# STM8S005C6_Footsprint.net
KiCad netlist of a schematic drawn in Altium Designer
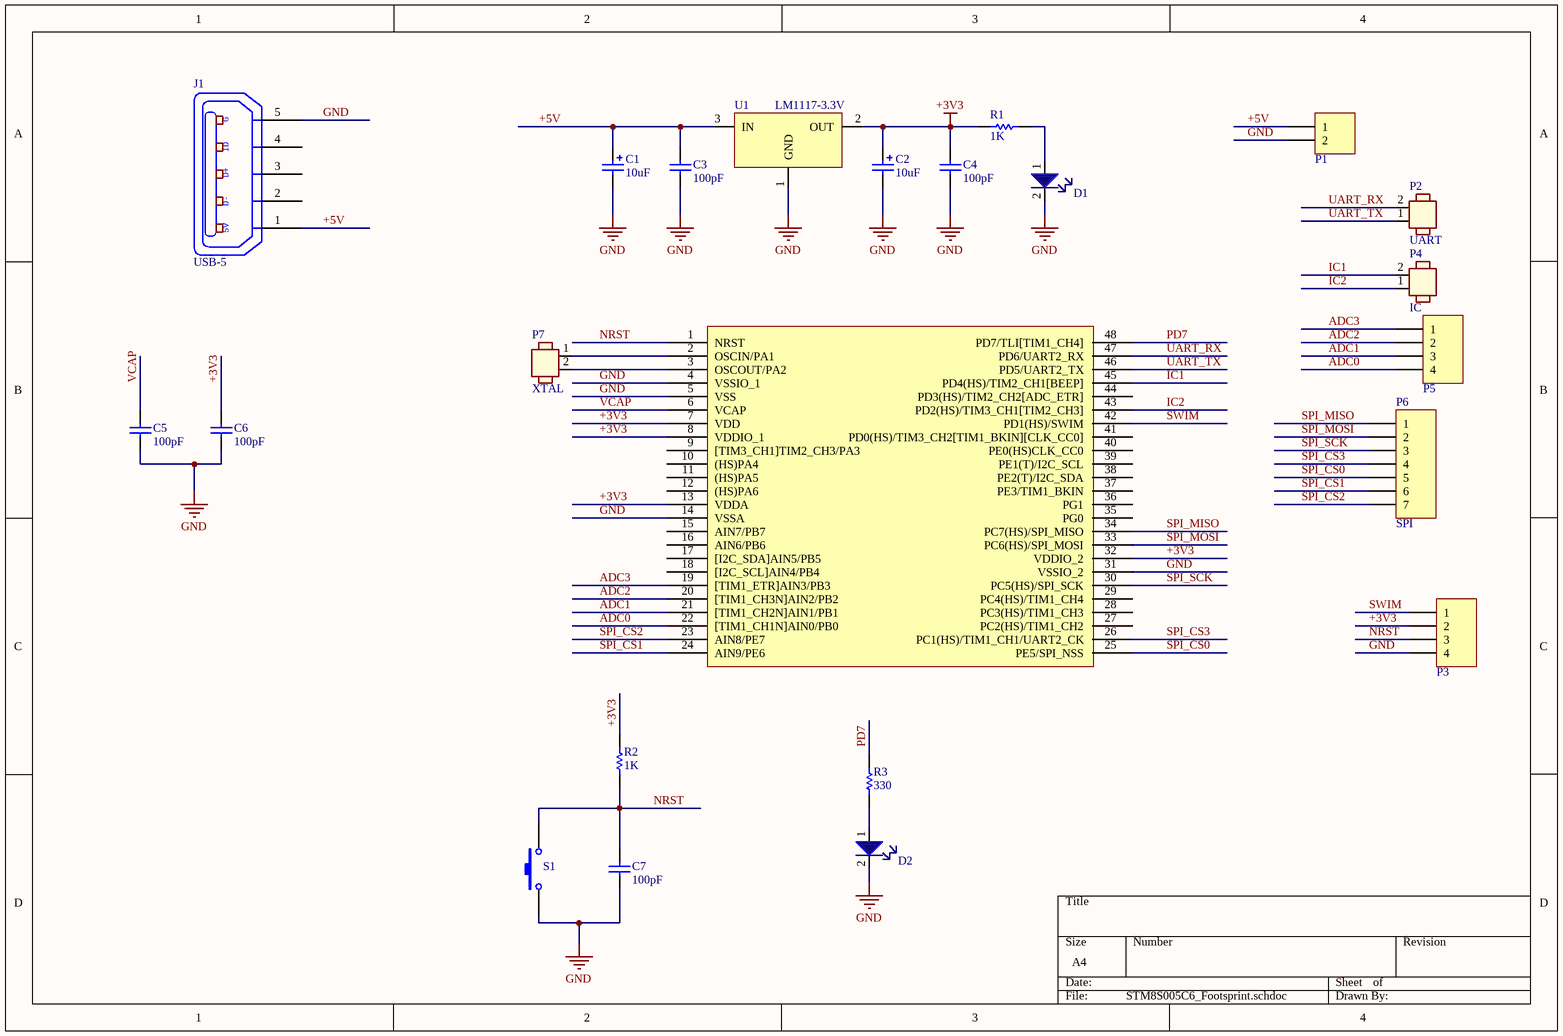
[diagram p0: STM8S005C6_Footsprint.schdoc]

(export (version "E")
  (design (tool "Eeschema 10.0.6"))
  (components
    (comp (ref "C1")
      (value "10uF")
      (footprint "CP1/2")
      (description "Polarized Capacitor (Radial)")
      (fields (field (name "Comment") "Cap Pol"))
      (libsource (lib "PIF_Library") (part "Cap Pol"))
    )
    (comp (ref "C2")
      (value "10uF")
      (footprint "CP1/2")
      (description "Polarized Capacitor (Radial)")
      (fields (field (name "Comment") "Cap Pol"))
      (libsource (lib "PIF_Library") (part "Cap Pol"))
    )
    (comp (ref "C3")
      (value "100pF")
      (footprint "CAP-SM-0805")
      (description "Capacitor")
      (fields (field (name "Comment") "Cap Non-Pol SMD"))
      (libsource (lib "PIF_Library") (part "Cap Non-Pol SMD"))
    )
    (comp (ref "C4")
      (value "100pF")
      (footprint "CAP-SM-0805")
      (description "Capacitor")
      (fields (field (name "Comment") "Cap Non-Pol SMD"))
      (libsource (lib "PIF_Library") (part "Cap Non-Pol SMD"))
    )
    (comp (ref "C5")
      (value "100pF")
      (footprint "CAP-SM-0805")
      (description "Capacitor")
      (fields (field (name "Comment") "Cap Non-Pol SMD"))
      (libsource (lib "PIF_Library") (part "Cap Non-Pol SMD"))
    )
    (comp (ref "C6")
      (value "100pF")
      (footprint "CAP-SM-0805")
      (description "Capacitor")
      (fields (field (name "Comment") "Cap Non-Pol SMD"))
      (libsource (lib "PIF_Library") (part "Cap Non-Pol SMD"))
    )
    (comp (ref "C7")
      (value "100pF")
      (footprint "CAP-SM-0805")
      (description "Capacitor")
      (fields (field (name "Comment") "Cap Non-Pol SMD"))
      (libsource (lib "PIF_Library") (part "Cap Non-Pol SMD"))
    )
    (comp (ref "D1") (value "LED") (footprint "LED 3mm") (libsource (lib "C15") (part "LED")))
    (comp (ref "D2") (value "LED") (footprint "LED 3mm") (libsource (lib "C15") (part "LED")))
    (comp (ref "J1")
      (value "USB-5")
      (footprint "USB-M2")
      (fields
        (field (name "MANUFACTURER") "FCI")
        (field (name "MANUFACTURER PART NUMBER") "10118193-0001LF")
        (field (name ".CREATOR") "MM")
        (field (name ".CHECKED PCB") "RF")
        (field (name ".CHECKED SCH") "MM")
      )
      (libsource (lib "LIBRARY") (part "USB-5"))
    )
    (comp (ref "P1")
      (value "Header 2")
      (footprint "JP2")
      (description "Header, 2-Pin")
      (fields (field (name "PUBLISHER") "Altium Limited"))
      (libsource (lib "PIF_Library") (part "Header 2"))
    )
    (comp (ref "P2") (value "UART") (footprint "HDR 2x1") (libsource (lib "C15") (part "Header 2")))
    (comp (ref "P3")
      (value "Header 4")
      (footprint "JP4")
      (description "Header, 4-Pin")
      (fields (field (name "PUBLISHER") "Altium Limited"))
      (libsource (lib "PIF_Library") (part "Header 4"))
    )
    (comp (ref "P4") (value "IC") (footprint "HDR 2x1") (libsource (lib "C15") (part "Header 2")))
    (comp (ref "P5")
      (value "Header 4")
      (footprint "JP4")
      (description "Header, 4-Pin")
      (fields (field (name "PUBLISHER") "Altium Limited"))
      (libsource (lib "PIF_Library") (part "Header 4"))
    )
    (comp (ref "P6")
      (value "SPI")
      (footprint "HDR1X7")
      (description "Header, 7-Pin")
      (fields (field (name "PUBLISHER") "Altium Limited"))
      (libsource (lib "NBBLib 14-03-2012") (part "Header 7"))
    )
    (comp (ref "P7") (value "XTAL") (footprint "HDR 2x1") (libsource (lib "") (part "Header 2_1")))
    (comp (ref "R1")
      (value "1K")
      (footprint "RES-SM-0805")
      (description "Resistor")
      (fields (field (name "Comment") "RESISTOR SMD"))
      (libsource (lib "PIF_Library") (part "RESISTOR SMD"))
    )
    (comp (ref "R2")
      (value "1K")
      (footprint "RES-SM-0805")
      (description "Resistor")
      (fields (field (name "Comment") "RESISTOR SMD"))
      (libsource (lib "PIF_Library") (part "RESISTOR SMD"))
    )
    (comp (ref "R3")
      (value "330")
      (footprint "RES-SM-0805")
      (description "Resistor")
      (fields (field (name "Comment") "RESISTOR SMD"))
      (libsource (lib "PIF_Library") (part "RESISTOR SMD"))
    )
    (comp (ref "S1")
      (value "Tact SW - 2Pin")
      (footprint "SW2")
      (description "Switch button 2 pin")
      (libsource (lib "PIF_Library") (part "Tact SW - 2Pin"))
    )
    (comp (ref "U1")
      (value "LM1117-3.3V")
      (footprint "SOT223")
      (description "800mA Low-Dropout Linear Regulator")
      (fields (field (name "CREATOR") "Nguyen Ba Bien"))
      (libsource (lib "LIBRARY") (part "LM1117"))
    )
    (comp (ref "U2")
      (value "STM8S005C6")
      (footprint "STM8S005C6")
      (libsource (lib "syhaunguyen") (part "STM8S005C6"))
    )
  )
  (nets
    (net (code "1") (name "+3V3") (class "Default")
      (node (ref "C2") (pin "1") (pinfunction "1_1") (pintype "passive"))
      (node (ref "C4") (pin "1") (pinfunction "1_1") (pintype "passive"))
      (node (ref "C6") (pin "1") (pinfunction "1_1") (pintype "passive"))
      (node (ref "P3") (pin "2") (pinfunction "2_2") (pintype "passive"))
      (node (ref "R1") (pin "1") (pinfunction "1_1") (pintype "passive"))
      (node (ref "R2") (pin "2") (pinfunction "2_2") (pintype "passive"))
      (node (ref "U1") (pin "2") (pinfunction "OUT_2") (pintype "passive"))
      (node (ref "U2") (pin "13") (pinfunction "VDDA_13") (pintype "passive"))
      (node (ref "U2") (pin "32") (pinfunction "VDDIO_2_32") (pintype "passive"))
      (node (ref "U2") (pin "7") (pinfunction "VDD_7") (pintype "passive"))
      (node (ref "U2") (pin "8") (pinfunction "VDDIO_1_8") (pintype "passive"))
    )
    (net (code "2") (name "/+5V") (class "Default")
      (node (ref "C1") (pin "1") (pinfunction "1_1") (pintype "passive"))
      (node (ref "C3") (pin "1") (pinfunction "1_1") (pintype "passive"))
      (node (ref "J1") (pin "1") (pinfunction "P1_1") (pintype "passive"))
      (node (ref "P1") (pin "1") (pinfunction "1_1") (pintype "passive"))
      (node (ref "U1") (pin "3") (pinfunction "IN_3") (pintype "passive"))
    )
    (net (code "3") (name "/ADC0") (class "Default")
      (node (ref "P5") (pin "4") (pinfunction "4_4") (pintype "passive"))
      (node (ref "U2") (pin "22") (pinfunction "[TIM1_CH1N]AIN0/PB0_22") (pintype "passive"))
    )
    (net (code "4") (name "/ADC1") (class "Default")
      (node (ref "P5") (pin "3") (pinfunction "3_3") (pintype "passive"))
      (node (ref "U2") (pin "21") (pinfunction "[TIM1_CH2N]AIN1/PB1_21") (pintype "passive"))
    )
    (net (code "5") (name "/ADC2") (class "Default")
      (node (ref "P5") (pin "2") (pinfunction "2_2") (pintype "passive"))
      (node (ref "U2") (pin "20") (pinfunction "[TIM1_CH3N]AIN2/PB2_20") (pintype "passive"))
    )
    (net (code "6") (name "/ADC3") (class "Default")
      (node (ref "P5") (pin "1") (pinfunction "1_1") (pintype "passive"))
      (node (ref "U2") (pin "19") (pinfunction "[TIM1_ETR]AIN3/PB3_19") (pintype "passive"))
    )
    (net (code "7") (name "/IC1") (class "Default")
      (node (ref "P4") (pin "2") (pinfunction "2_2") (pintype "passive"))
      (node (ref "U2") (pin "45") (pinfunction "PD4(HS)/TIM2_CH1[BEEP]_45") (pintype "passive"))
    )
    (net (code "8") (name "/IC2") (class "Default")
      (node (ref "P4") (pin "1") (pinfunction "1_1") (pintype "passive"))
      (node (ref "U2") (pin "43") (pinfunction "PD2(HS)/TIM3_CH1[TIM2_CH3]_43") (pintype "passive"))
    )
    (net (code "9") (name "/NRST") (class "Default")
      (node (ref "C7") (pin "1") (pinfunction "1_1") (pintype "passive"))
      (node (ref "P3") (pin "3") (pinfunction "3_3") (pintype "passive"))
      (node (ref "R2") (pin "1") (pinfunction "1_1") (pintype "passive"))
      (node (ref "S1") (pin "2") (pinfunction "2_2") (pintype "passive"))
      (node (ref "U2") (pin "1") (pinfunction "NRST_1") (pintype "passive"))
    )
    (net (code "10") (name "/PD7") (class "Default")
      (node (ref "R3") (pin "2") (pinfunction "2_2") (pintype "passive"))
      (node (ref "U2") (pin "48") (pinfunction "PD7/TLI[TIM1_CH4]_48") (pintype "passive"))
    )
    (net (code "11") (name "/SPI_CS0") (class "Default")
      (node (ref "P6") (pin "5") (pinfunction "5_5") (pintype "passive"))
      (node (ref "U2") (pin "25") (pinfunction "PE5/SPI_NSS_25") (pintype "passive"))
    )
    (net (code "12") (name "/SPI_CS1") (class "Default")
      (node (ref "P6") (pin "6") (pinfunction "6_6") (pintype "passive"))
      (node (ref "U2") (pin "24") (pinfunction "AIN9/PE6_24") (pintype "passive"))
    )
    (net (code "13") (name "/SPI_CS2") (class "Default")
      (node (ref "P6") (pin "7") (pinfunction "7_7") (pintype "passive"))
      (node (ref "U2") (pin "23") (pinfunction "AIN8/PE7_23") (pintype "passive"))
    )
    (net (code "14") (name "/SPI_CS3") (class "Default")
      (node (ref "P6") (pin "4") (pinfunction "4_4") (pintype "passive"))
      (node (ref "U2") (pin "26") (pinfunction "PC1(HS)/TIM1_CH1/UART2_CK_26") (pintype "passive"))
    )
    (net (code "15") (name "/SPI_MISO") (class "Default")
      (node (ref "P6") (pin "1") (pinfunction "1_1") (pintype "passive"))
      (node (ref "U2") (pin "34") (pinfunction "PC7(HS)/SPI_MISO_34") (pintype "passive"))
    )
    (net (code "16") (name "/SPI_MOSI") (class "Default")
      (node (ref "P6") (pin "2") (pinfunction "2_2") (pintype "passive"))
      (node (ref "U2") (pin "33") (pinfunction "PC6(HS)/SPI_MOSI_33") (pintype "passive"))
    )
    (net (code "17") (name "/SPI_SCK") (class "Default")
      (node (ref "P6") (pin "3") (pinfunction "3_3") (pintype "passive"))
      (node (ref "U2") (pin "30") (pinfunction "PC5(HS)/SPI_SCK_30") (pintype "passive"))
    )
    (net (code "18") (name "/SWIM") (class "Default")
      (node (ref "P3") (pin "1") (pinfunction "1_1") (pintype "passive"))
      (node (ref "U2") (pin "42") (pinfunction "PD1(HS)/SWIM_42") (pintype "passive"))
    )
    (net (code "19") (name "/UART_RX") (class "Default")
      (node (ref "P2") (pin "2") (pinfunction "2_2") (pintype "passive"))
      (node (ref "U2") (pin "47") (pinfunction "PD6/UART2_RX_47") (pintype "passive"))
    )
    (net (code "20") (name "/UART_TX") (class "Default")
      (node (ref "P2") (pin "1") (pinfunction "1_1") (pintype "passive"))
      (node (ref "U2") (pin "46") (pinfunction "PD5/UART2_TX_46") (pintype "passive"))
    )
    (net (code "21") (name "/VCAP") (class "Default")
      (node (ref "C5") (pin "1") (pinfunction "1_1") (pintype "passive"))
      (node (ref "U2") (pin "6") (pinfunction "VCAP_6") (pintype "passive"))
    )
    (net (code "22") (name "GND") (class "Default")
      (node (ref "C1") (pin "2") (pinfunction "2_2") (pintype "passive"))
      (node (ref "C2") (pin "2") (pinfunction "2_2") (pintype "passive"))
      (node (ref "C3") (pin "2") (pinfunction "2_2") (pintype "passive"))
      (node (ref "C4") (pin "2") (pinfunction "2_2") (pintype "passive"))
      (node (ref "C5") (pin "2") (pinfunction "2_2") (pintype "passive"))
      (node (ref "C6") (pin "2") (pinfunction "2_2") (pintype "passive"))
      (node (ref "C7") (pin "2") (pinfunction "2_2") (pintype "passive"))
      (node (ref "D1") (pin "2") (pintype "passive"))
      (node (ref "D2") (pin "2") (pintype "passive"))
      (node (ref "J1") (pin "5") (pinfunction "P5_5") (pintype "passive"))
      (node (ref "P1") (pin "2") (pinfunction "2_2") (pintype "passive"))
      (node (ref "P3") (pin "4") (pinfunction "4_4") (pintype "passive"))
      (node (ref "S1") (pin "1") (pinfunction "1_1") (pintype "passive"))
      (node (ref "U1") (pin "1") (pinfunction "GND_1") (pintype "passive"))
      (node (ref "U2") (pin "14") (pinfunction "VSSA_14") (pintype "passive"))
      (node (ref "U2") (pin "31") (pinfunction "VSSIO_2_31") (pintype "passive"))
      (node (ref "U2") (pin "4") (pinfunction "VSSIO_1_4") (pintype "passive"))
      (node (ref "U2") (pin "5") (pinfunction "VSS_5") (pintype "passive"))
    )
    (net (code "23") (name "Net-(D1-Pad1)") (class "Default")
      (node (ref "D1") (pin "1") (pintype "passive"))
      (node (ref "R1") (pin "2") (pinfunction "2_2") (pintype "passive"))
    )
    (net (code "24") (name "Net-(D2-Pad1)") (class "Default")
      (node (ref "D2") (pin "1") (pintype "passive"))
      (node (ref "R3") (pin "1") (pinfunction "1_1") (pintype "passive"))
    )
    (net (code "25") (name "Net-(U2-OSCIN{slash}PA1)") (class "Default")
      (node (ref "P7") (pin "1") (pinfunction "1_1") (pintype "passive"))
      (node (ref "U2") (pin "2") (pinfunction "OSCIN/PA1_2") (pintype "passive"))
    )
    (net (code "26") (name "Net-(U2-OSCOUT{slash}PA2)") (class "Default")
      (node (ref "P7") (pin "2") (pinfunction "2_2") (pintype "passive"))
      (node (ref "U2") (pin "3") (pinfunction "OSCOUT/PA2_3") (pintype "passive"))
    )
    (net (code "27") (name "unconnected-(J1-P2-Pad2)") (class "Default")
      (node (ref "J1") (pin "2") (pinfunction "P2_2") (pintype "passive"))
    )
    (net (code "28") (name "unconnected-(J1-P3-Pad3)") (class "Default")
      (node (ref "J1") (pin "3") (pinfunction "P3_3") (pintype "passive"))
    )
    (net (code "29") (name "unconnected-(J1-P4-Pad4)") (class "Default")
      (node (ref "J1") (pin "4") (pinfunction "P4_4") (pintype "passive"))
    )
    (net (code "30") (name "unconnected-(U2-(HS)PA4-Pad10)") (class "Default")
      (node (ref "U2") (pin "10") (pinfunction "(HS)PA4_10") (pintype "passive"))
    )
    (net (code "31") (name "unconnected-(U2-(HS)PA5-Pad11)") (class "Default")
      (node (ref "U2") (pin "11") (pinfunction "(HS)PA5_11") (pintype "passive"))
    )
    (net (code "32") (name "unconnected-(U2-(HS)PA6-Pad12)") (class "Default")
      (node (ref "U2") (pin "12") (pinfunction "(HS)PA6_12") (pintype "passive"))
    )
    (net (code "33") (name "unconnected-(U2-AIN6{slash}PB6-Pad16)") (class "Default")
      (node (ref "U2") (pin "16") (pinfunction "AIN6/PB6_16") (pintype "passive"))
    )
    (net (code "34") (name "unconnected-(U2-AIN7{slash}PB7-Pad15)") (class "Default")
      (node (ref "U2") (pin "15") (pinfunction "AIN7/PB7_15") (pintype "passive"))
    )
    (net (code "35") (name "unconnected-(U2-PC2(HS){slash}TIM1_CH2-Pad27)") (class "Default")
      (node (ref "U2") (pin "27") (pinfunction "PC2(HS)/TIM1_CH2_27") (pintype "passive"))
    )
    (net (code "36") (name "unconnected-(U2-PC3(HS){slash}TIM1_CH3-Pad28)") (class "Default")
      (node (ref "U2") (pin "28") (pinfunction "PC3(HS)/TIM1_CH3_28") (pintype "passive"))
    )
    (net (code "37") (name "unconnected-(U2-PC4(HS){slash}TIM1_CH4-Pad29)") (class "Default")
      (node (ref "U2") (pin "29") (pinfunction "PC4(HS)/TIM1_CH4_29") (pintype "passive"))
    )
    (net (code "38") (name "unconnected-(U2-PD0(HS){slash}TIM3_CH2[TIM1_BKIN][CLK_CC0]-Pad41)") (class "Default")
      (node (ref "U2") (pin "41") (pinfunction "PD0(HS)/TIM3_CH2[TIM1_BKIN][CLK_CC0]_41") (pintype "passive"))
    )
    (net (code "39") (name "unconnected-(U2-PD3(HS){slash}TIM2_CH2[ADC_ETR]-Pad44)") (class "Default")
      (node (ref "U2") (pin "44") (pinfunction "PD3(HS)/TIM2_CH2[ADC_ETR]_44") (pintype "passive"))
    )
    (net (code "40") (name "unconnected-(U2-PE0(HS)CLK_CC0-Pad40)") (class "Default")
      (node (ref "U2") (pin "40") (pinfunction "PE0(HS)CLK_CC0_40") (pintype "passive"))
    )
    (net (code "41") (name "unconnected-(U2-PE1(T){slash}I2C_SCL-Pad39)") (class "Default")
      (node (ref "U2") (pin "39") (pinfunction "PE1(T)/I2C_SCL_39") (pintype "passive"))
    )
    (net (code "42") (name "unconnected-(U2-PE2(T){slash}I2C_SDA-Pad38)") (class "Default")
      (node (ref "U2") (pin "38") (pinfunction "PE2(T)/I2C_SDA_38") (pintype "passive"))
    )
    (net (code "43") (name "unconnected-(U2-PE3{slash}TIM1_BKIN-Pad37)") (class "Default")
      (node (ref "U2") (pin "37") (pinfunction "PE3/TIM1_BKIN_37") (pintype "passive"))
    )
    (net (code "44") (name "unconnected-(U2-PG0-Pad35)") (class "Default")
      (node (ref "U2") (pin "35") (pinfunction "PG0_35") (pintype "passive"))
    )
    (net (code "45") (name "unconnected-(U2-PG1-Pad36)") (class "Default")
      (node (ref "U2") (pin "36") (pinfunction "PG1_36") (pintype "passive"))
    )
    (net (code "46") (name "unconnected-(U2-[I2C_SCL]AIN4{slash}PB4-Pad18)") (class "Default")
      (node (ref "U2") (pin "18") (pinfunction "[I2C_SCL]AIN4/PB4_18") (pintype "passive"))
    )
    (net (code "47") (name "unconnected-(U2-[I2C_SDA]AIN5{slash}PB5-Pad17)") (class "Default")
      (node (ref "U2") (pin "17") (pinfunction "[I2C_SDA]AIN5/PB5_17") (pintype "passive"))
    )
    (net (code "48") (name "unconnected-(U2-[TIM3_CH1]TIM2_CH3{slash}PA3-Pad9)") (class "Default")
      (node (ref "U2") (pin "9") (pinfunction "[TIM3_CH1]TIM2_CH3/PA3_9") (pintype "passive"))
    )
  )
)
